# Sheet1.net
KiCad netlist of a schematic drawn in Altium Designer
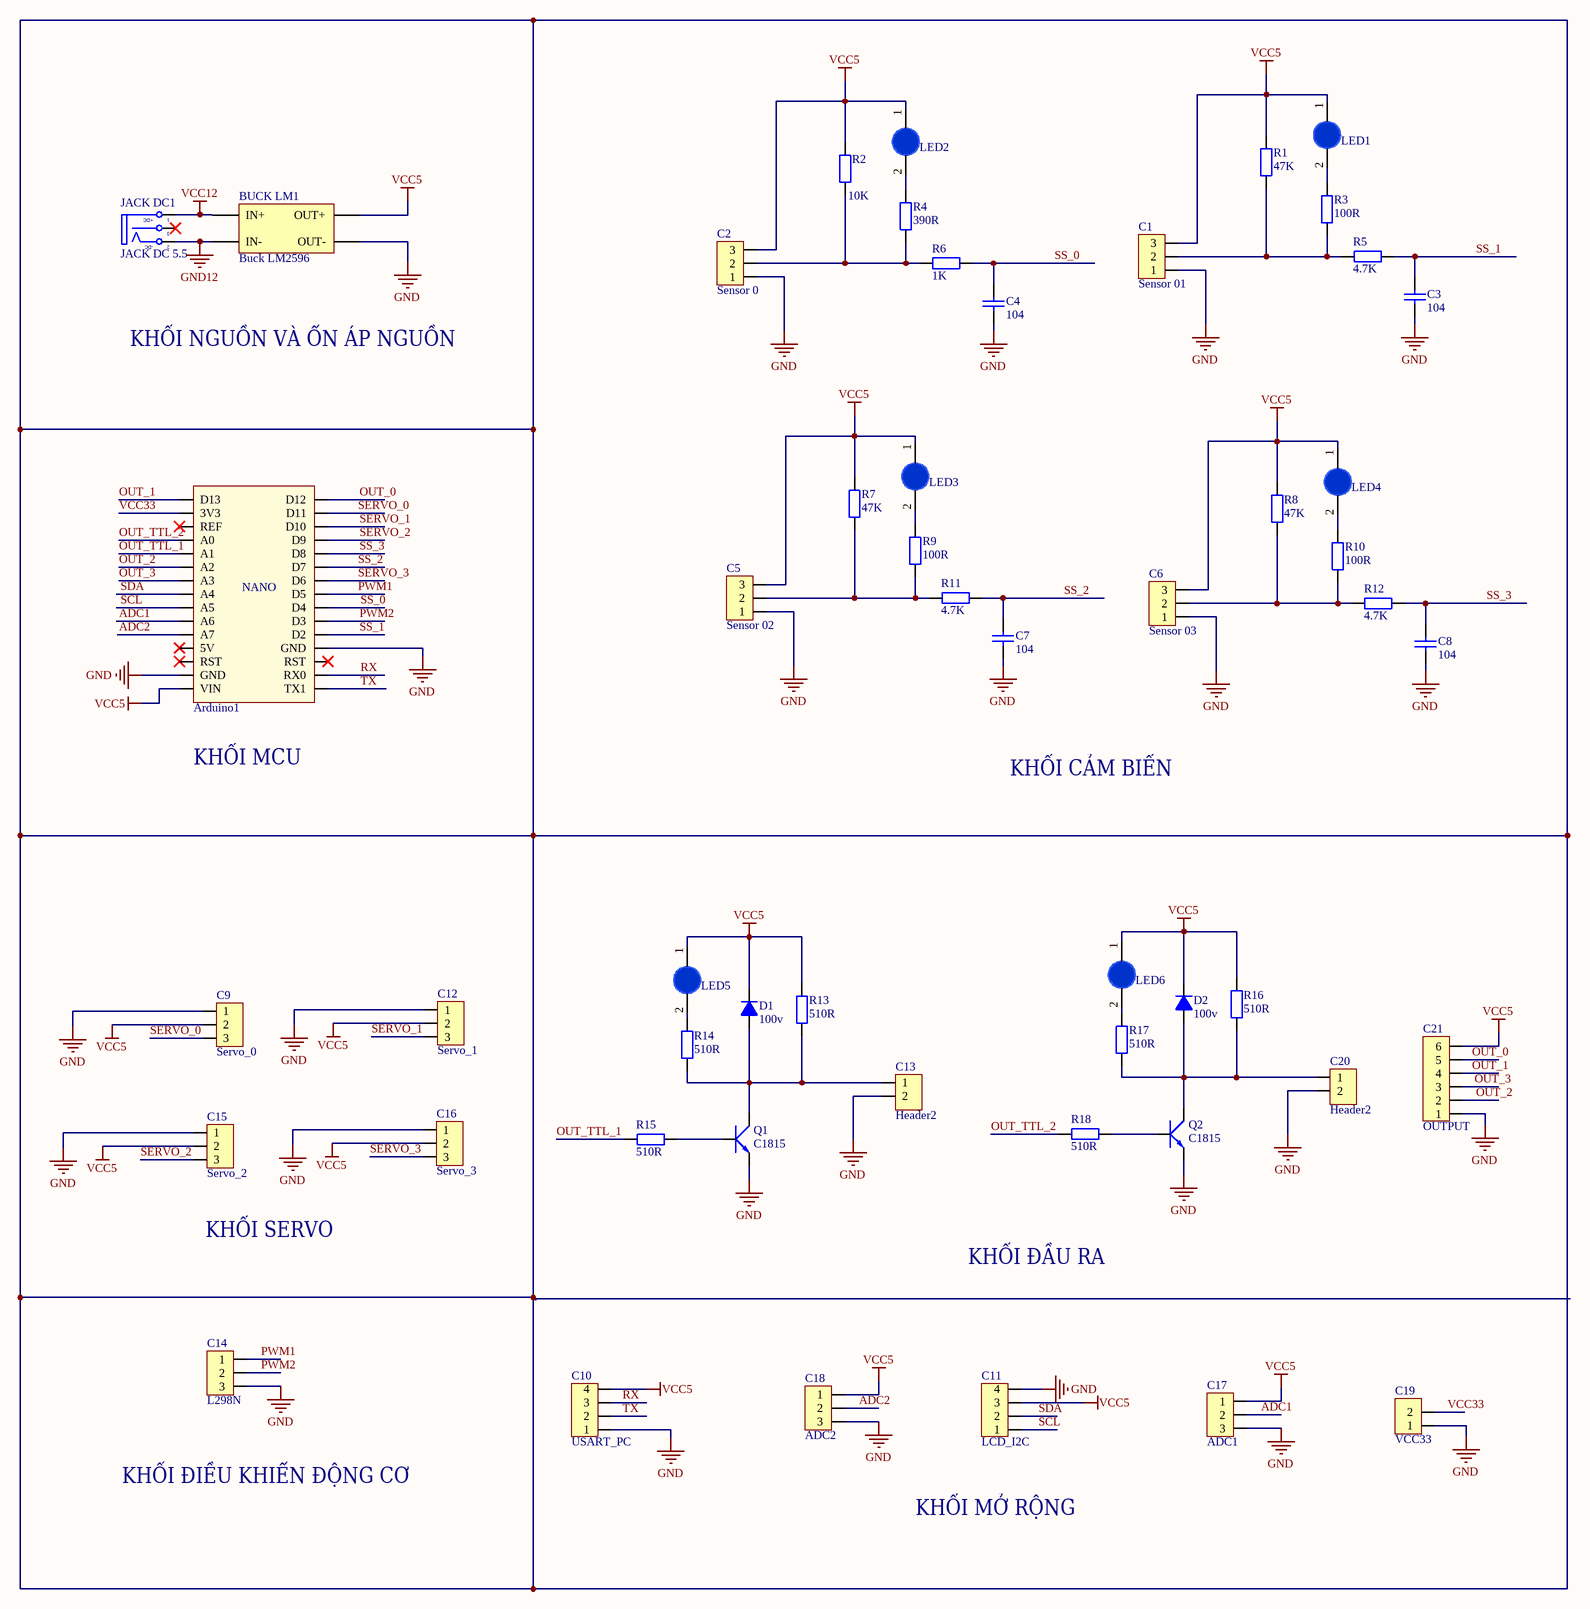
[diagram p0: Sheet1.SchDoc]

(export (version "E")
  (design (tool "Eeschema 10.0.6"))
  (components
    (comp (ref "Arduino1")
      (value "Arduino Nano")
      (footprint "Arduino Nano")
      (description "Arduino NANO")
      (libsource (lib "myLib_v1") (part "Arduino Nano"))
    )
    (comp (ref "BUCK LM1")
      (value "Buck LM2596")
      (footprint "BUCK LM2596")
      (libsource (lib "myLib_v1") (part "Buck LM2596"))
    )
    (comp (ref "C1")
      (value "Sensor 01")
      (footprint "Header3")
      (description "Header IDC, 3 x 1 Pin Vertical 2.54mm Pitch (Non-Boxed, Male)")
      (fields
        (field (name "MANUFACTURER") "Würth Elektronik eiSos GmbH")
        (field (name "PARTNO") "613002143121")
        (field (name "CREATED BY") "Karrer Zheng")
      )
      (libsource (lib "myLib_v1") (part "Header3"))
    )
    (comp (ref "C2")
      (value "Sensor 0")
      (footprint "Header3")
      (description "Header IDC, 3 x 1 Pin Vertical 2.54mm Pitch (Non-Boxed, Male)")
      (fields
        (field (name "MANUFACTURER") "Würth Elektronik eiSos GmbH")
        (field (name "PARTNO") "613002143121")
        (field (name "CREATED BY") "Karrer Zheng")
      )
      (libsource (lib "myLib_v1") (part "Header3"))
    )
    (comp (ref "C3")
      (value "104")
      (footprint "tu gom")
      (description "Cắm")
      (libsource (lib "Altium_Lib_by_KhueNguyenCreator") (part "Tu gom 104 50V"))
    )
    (comp (ref "C4")
      (value "104")
      (footprint "tu gom")
      (description "Cắm")
      (libsource (lib "Altium_Lib_by_KhueNguyenCreator") (part "Tu gom 104 50V"))
    )
    (comp (ref "C5")
      (value "Sensor 02")
      (footprint "Header3")
      (description "Header IDC, 3 x 1 Pin Vertical 2.54mm Pitch (Non-Boxed, Male)")
      (fields
        (field (name "MANUFACTURER") "Würth Elektronik eiSos GmbH")
        (field (name "PARTNO") "613002143121")
        (field (name "CREATED BY") "Karrer Zheng")
      )
      (libsource (lib "myLib_v1") (part "Header3"))
    )
    (comp (ref "C6")
      (value "Sensor 03")
      (footprint "Header3")
      (description "Header IDC, 3 x 1 Pin Vertical 2.54mm Pitch (Non-Boxed, Male)")
      (fields
        (field (name "MANUFACTURER") "Würth Elektronik eiSos GmbH")
        (field (name "PARTNO") "613002143121")
        (field (name "CREATED BY") "Karrer Zheng")
      )
      (libsource (lib "myLib_v1") (part "Header3"))
    )
    (comp (ref "C7")
      (value "104")
      (footprint "tu gom")
      (description "Cắm")
      (libsource (lib "Altium_Lib_by_KhueNguyenCreator") (part "Tu gom 104 50V"))
    )
    (comp (ref "C8")
      (value "104")
      (footprint "tu gom")
      (description "Cắm")
      (libsource (lib "Altium_Lib_by_KhueNguyenCreator") (part "Tu gom 104 50V"))
    )
    (comp (ref "C9")
      (value "Servo_0")
      (footprint "Header3")
      (description "Header IDC, 3 x 1 Pin Vertical 2.54mm Pitch (Non-Boxed, Male)")
      (fields
        (field (name "MANUFACTURER") "Würth Elektronik eiSos GmbH")
        (field (name "PARTNO") "613002143121")
        (field (name "CREATED BY") "Karrer Zheng")
      )
      (libsource (lib "") (part "Header3_1"))
    )
    (comp (ref "C10")
      (value "USART_PC")
      (footprint "Header4")
      (description "Header IDC, 4 x 1 Pin Vertical 2.54mm Pitch (Non-Boxed, Male)")
      (fields
        (field (name "MANUFACTURER") "Würth Elektronik eiSos GmbH")
        (field (name "PARTNO") "613002143121")
        (field (name "CREATED BY") "Karrer Zheng")
      )
      (libsource (lib "myLib_v1") (part "Header4"))
    )
    (comp (ref "C11")
      (value "LCD_I2C")
      (footprint "Header4")
      (description "Header IDC, 4 x 1 Pin Vertical 2.54mm Pitch (Non-Boxed, Male)")
      (fields
        (field (name "MANUFACTURER") "Würth Elektronik eiSos GmbH")
        (field (name "PARTNO") "613002143121")
        (field (name "CREATED BY") "Karrer Zheng")
      )
      (libsource (lib "myLib_v1") (part "Header4"))
    )
    (comp (ref "C12")
      (value "Servo_1")
      (footprint "Header3")
      (description "Header IDC, 3 x 1 Pin Vertical 2.54mm Pitch (Non-Boxed, Male)")
      (fields
        (field (name "MANUFACTURER") "Würth Elektronik eiSos GmbH")
        (field (name "PARTNO") "613002143121")
        (field (name "CREATED BY") "Karrer Zheng")
      )
      (libsource (lib "") (part "Header3_1"))
    )
    (comp (ref "C13")
      (value "Header2")
      (footprint "Header2")
      (description "Header IDC, 2 x 1 Pin Vertical 2.54mm Pitch (Non-Boxed, Male)")
      (fields
        (field (name "MANUFACTURER") "Würth Elektronik eiSos GmbH")
        (field (name "PARTNO") "613002143121")
        (field (name "CREATED BY") "Karrer Zheng")
      )
      (libsource (lib "myLib_v1") (part "Header2"))
    )
    (comp (ref "C14")
      (value "L298N")
      (footprint "Header3")
      (description "Header IDC, 3 x 1 Pin Vertical 2.54mm Pitch (Non-Boxed, Male)")
      (fields
        (field (name "MANUFACTURER") "Würth Elektronik eiSos GmbH")
        (field (name "PARTNO") "613002143121")
        (field (name "CREATED BY") "Karrer Zheng")
      )
      (libsource (lib "") (part "Header3_2"))
    )
    (comp (ref "C15")
      (value "Servo_2")
      (footprint "Header3")
      (description "Header IDC, 3 x 1 Pin Vertical 2.54mm Pitch (Non-Boxed, Male)")
      (fields
        (field (name "MANUFACTURER") "Würth Elektronik eiSos GmbH")
        (field (name "PARTNO") "613002143121")
        (field (name "CREATED BY") "Karrer Zheng")
      )
      (libsource (lib "") (part "Header3_1"))
    )
    (comp (ref "C16")
      (value "Servo_3")
      (footprint "Header3")
      (description "Header IDC, 3 x 1 Pin Vertical 2.54mm Pitch (Non-Boxed, Male)")
      (fields
        (field (name "MANUFACTURER") "Würth Elektronik eiSos GmbH")
        (field (name "PARTNO") "613002143121")
        (field (name "CREATED BY") "Karrer Zheng")
      )
      (libsource (lib "") (part "Header3_1"))
    )
    (comp (ref "C17")
      (value "ADC1")
      (footprint "Header3")
      (description "Header IDC, 3 x 1 Pin Vertical 2.54mm Pitch (Non-Boxed, Male)")
      (fields
        (field (name "MANUFACTURER") "Würth Elektronik eiSos GmbH")
        (field (name "PARTNO") "613002143121")
        (field (name "CREATED BY") "Karrer Zheng")
      )
      (libsource (lib "") (part "Header3_2"))
    )
    (comp (ref "C18")
      (value "ADC2")
      (footprint "Header3")
      (description "Header IDC, 3 x 1 Pin Vertical 2.54mm Pitch (Non-Boxed, Male)")
      (fields
        (field (name "MANUFACTURER") "Würth Elektronik eiSos GmbH")
        (field (name "PARTNO") "613002143121")
        (field (name "CREATED BY") "Karrer Zheng")
      )
      (libsource (lib "") (part "Header3_2"))
    )
    (comp (ref "C19")
      (value "VCC33")
      (footprint "Header2")
      (description "Header IDC, 2 x 1 Pin Vertical 2.54mm Pitch (Non-Boxed, Male)")
      (fields
        (field (name "MANUFACTURER") "Würth Elektronik eiSos GmbH")
        (field (name "PARTNO") "613002143121")
        (field (name "CREATED BY") "Karrer Zheng")
      )
      (libsource (lib "") (part "Header2_1"))
    )
    (comp (ref "C20")
      (value "Header2")
      (footprint "Header2")
      (description "Header IDC, 2 x 1 Pin Vertical 2.54mm Pitch (Non-Boxed, Male)")
      (fields
        (field (name "MANUFACTURER") "Würth Elektronik eiSos GmbH")
        (field (name "PARTNO") "613002143121")
        (field (name "CREATED BY") "Karrer Zheng")
      )
      (libsource (lib "myLib_v1") (part "Header2"))
    )
    (comp (ref "C21")
      (value "OUTPUT")
      (footprint "Header6")
      (description "Header IDC, 6 x 1 Pin Vertical 2.54mm Pitch (Non-Boxed, Male)")
      (fields
        (field (name "MANUFACTURER") "Würth Elektronik eiSos GmbH")
        (field (name "PARTNO") "613002143121")
        (field (name "CREATED BY") "Karrer Zheng")
      )
      (libsource (lib "myLib_v1") (part "Header6"))
    )
    (comp (ref "D1")
      (value "100v")
      (footprint "DIODE 0.5A")
      (description "Cắm")
      (libsource (lib "Altium_Lib_by_KhueNguyenCreator") (part "Diode 1N4148"))
    )
    (comp (ref "D2")
      (value "100v")
      (footprint "DIODE 0.5A")
      (description "Cắm")
      (libsource (lib "Altium_Lib_by_KhueNguyenCreator") (part "Diode 1N4148"))
    )
    (comp (ref "JACK DC1")
      (value "JACK DC 5.5")
      (footprint "JACK DC 5.5")
      (libsource (lib "Altium_Lib_by_KhueNguyenCreator") (part "JACK DC 5.5"))
    )
    (comp (ref "LED1")
      (value "LED 3mm")
      (footprint "LED-3MM-BLUE")
      (description "Cắm")
      (libsource (lib "myLib_v1") (part "LED 3mm Xanh Duong"))
    )
    (comp (ref "LED2")
      (value "LED 3mm")
      (footprint "LED-3MM-BLUE")
      (description "Cắm")
      (libsource (lib "myLib_v1") (part "LED 3mm Xanh Duong"))
    )
    (comp (ref "LED3")
      (value "LED 3mm")
      (footprint "LED-3MM-BLUE")
      (description "Cắm")
      (libsource (lib "myLib_v1") (part "LED 3mm Xanh Duong"))
    )
    (comp (ref "LED4")
      (value "LED 3mm")
      (footprint "LED-3MM-BLUE")
      (description "Cắm")
      (libsource (lib "myLib_v1") (part "LED 3mm Xanh Duong"))
    )
    (comp (ref "LED5")
      (value "LED 3mm")
      (footprint "LED-3MM-BLUE")
      (description "Cắm")
      (libsource (lib "myLib_v1") (part "LED 3mm Xanh Duong"))
    )
    (comp (ref "LED6")
      (value "LED 3mm")
      (footprint "LED-3MM-BLUE")
      (description "Cắm")
      (libsource (lib "myLib_v1") (part "LED 3mm Xanh Duong"))
    )
    (comp (ref "Q1")
      (value "C1815")
      (footprint "C1815_cam")
      (description "NPN 600mW, ECB")
      (libsource (lib "myLib_v1") (part "C1815"))
    )
    (comp (ref "Q2")
      (value "C1815")
      (footprint "C1815_cam")
      (description "NPN 600mW, ECB")
      (libsource (lib "myLib_v1") (part "C1815"))
    )
    (comp (ref "R1")
      (value "47K")
      (footprint "R1/4W")
      (description "Resistor 1/4W")
      (libsource (lib "myLib_v1") (part "R1/4W"))
    )
    (comp (ref "R2")
      (value "10K")
      (footprint "R1/4W")
      (description "Resistor 1/4W")
      (libsource (lib "myLib_v1") (part "R1/4W"))
    )
    (comp (ref "R3")
      (value "100R")
      (footprint "R1/4W")
      (description "Resistor 1/4W")
      (libsource (lib "myLib_v1") (part "R1/4W"))
    )
    (comp (ref "R4")
      (value "390R")
      (footprint "R1/4W")
      (description "Resistor 1/4W")
      (libsource (lib "myLib_v1") (part "R1/4W"))
    )
    (comp (ref "R5")
      (value "4.7K")
      (footprint "R1/4W")
      (description "Resistor 1/4W")
      (libsource (lib "myLib_v1") (part "R1/4W"))
    )
    (comp (ref "R6")
      (value "1K")
      (footprint "R1/4W")
      (description "Resistor 1/4W")
      (libsource (lib "myLib_v1") (part "R1/4W"))
    )
    (comp (ref "R7")
      (value "47K")
      (footprint "R1/4W")
      (description "Resistor 1/4W")
      (libsource (lib "myLib_v1") (part "R1/4W"))
    )
    (comp (ref "R8")
      (value "47K")
      (footprint "R1/4W")
      (description "Resistor 1/4W")
      (libsource (lib "myLib_v1") (part "R1/4W"))
    )
    (comp (ref "R9")
      (value "100R")
      (footprint "R1/4W")
      (description "Resistor 1/4W")
      (libsource (lib "myLib_v1") (part "R1/4W"))
    )
    (comp (ref "R10")
      (value "100R")
      (footprint "R1/4W")
      (description "Resistor 1/4W")
      (libsource (lib "myLib_v1") (part "R1/4W"))
    )
    (comp (ref "R11")
      (value "4.7K")
      (footprint "R1/4W")
      (description "Resistor 1/4W")
      (libsource (lib "myLib_v1") (part "R1/4W"))
    )
    (comp (ref "R12")
      (value "4.7K")
      (footprint "R1/4W")
      (description "Resistor 1/4W")
      (libsource (lib "myLib_v1") (part "R1/4W"))
    )
    (comp (ref "R13")
      (value "510R")
      (footprint "R1/4W")
      (description "Resistor 1/4W")
      (libsource (lib "myLib_v1") (part "R1/4W"))
    )
    (comp (ref "R14")
      (value "510R")
      (footprint "R1/4W")
      (description "Resistor 1/4W")
      (libsource (lib "myLib_v1") (part "R1/4W"))
    )
    (comp (ref "R15")
      (value "510R")
      (footprint "R1/4W")
      (description "Resistor 1/4W")
      (libsource (lib "myLib_v1") (part "R1/4W"))
    )
    (comp (ref "R16")
      (value "510R")
      (footprint "R1/4W")
      (description "Resistor 1/4W")
      (libsource (lib "myLib_v1") (part "R1/4W"))
    )
    (comp (ref "R17")
      (value "510R")
      (footprint "R1/4W")
      (description "Resistor 1/4W")
      (libsource (lib "myLib_v1") (part "R1/4W"))
    )
    (comp (ref "R18")
      (value "510R")
      (footprint "R1/4W")
      (description "Resistor 1/4W")
      (libsource (lib "myLib_v1") (part "R1/4W"))
    )
  )
  (nets
    (net (code "1") (name "/ADC1") (class "Default")
      (node (ref "Arduino1") (pin "A6") (pinfunction "A6_A6") (pintype "passive"))
      (node (ref "C17") (pin "2") (pinfunction "2_2") (pintype "passive"))
    )
    (net (code "2") (name "/ADC2") (class "Default")
      (node (ref "Arduino1") (pin "A7") (pinfunction "A7_A7") (pintype "passive"))
      (node (ref "C18") (pin "2") (pinfunction "2_2") (pintype "passive"))
    )
    (net (code "3") (name "/OUT_0") (class "Default")
      (node (ref "Arduino1") (pin "D12") (pinfunction "D12_D12") (pintype "passive"))
      (node (ref "C21") (pin "5") (pinfunction "5_5") (pintype "passive"))
    )
    (net (code "4") (name "/OUT_1") (class "Default")
      (node (ref "Arduino1") (pin "D13") (pinfunction "D13_D13") (pintype "passive"))
      (node (ref "C21") (pin "4") (pinfunction "4_4") (pintype "passive"))
    )
    (net (code "5") (name "/OUT_2") (class "Default")
      (node (ref "Arduino1") (pin "A2") (pinfunction "A2_A2") (pintype "passive"))
      (node (ref "C21") (pin "2") (pinfunction "2_2") (pintype "passive"))
    )
    (net (code "6") (name "/OUT_3") (class "Default")
      (node (ref "Arduino1") (pin "A3") (pinfunction "A3_A3") (pintype "passive"))
      (node (ref "C21") (pin "3") (pinfunction "3_3") (pintype "passive"))
    )
    (net (code "7") (name "/OUT_TTL_1") (class "Default")
      (node (ref "Arduino1") (pin "A1") (pinfunction "A1_A1") (pintype "passive"))
      (node (ref "R15") (pin "1") (pinfunction "1_1") (pintype "passive"))
    )
    (net (code "8") (name "/OUT_TTL_2") (class "Default")
      (node (ref "Arduino1") (pin "A0") (pinfunction "A0_A0") (pintype "passive"))
      (node (ref "R18") (pin "1") (pinfunction "1_1") (pintype "passive"))
    )
    (net (code "9") (name "/PWM1") (class "Default")
      (node (ref "Arduino1") (pin "D5") (pinfunction "D5_D5") (pintype "passive"))
      (node (ref "C14") (pin "1") (pinfunction "1_1") (pintype "passive"))
    )
    (net (code "10") (name "/PWM2") (class "Default")
      (node (ref "Arduino1") (pin "D3") (pinfunction "D3_D3") (pintype "passive"))
      (node (ref "C14") (pin "2") (pinfunction "2_2") (pintype "passive"))
    )
    (net (code "11") (name "/RX") (class "Default")
      (node (ref "Arduino1") (pin "RX0") (pinfunction "RX0_RX0") (pintype "passive"))
      (node (ref "C10") (pin "3") (pinfunction "3_3") (pintype "passive"))
    )
    (net (code "12") (name "/SCL") (class "Default")
      (node (ref "Arduino1") (pin "A5") (pinfunction "A5_A5") (pintype "passive"))
      (node (ref "C11") (pin "1") (pinfunction "1_1") (pintype "passive"))
    )
    (net (code "13") (name "/SDA") (class "Default")
      (node (ref "Arduino1") (pin "A4") (pinfunction "A4_A4") (pintype "passive"))
      (node (ref "C11") (pin "2") (pinfunction "2_2") (pintype "passive"))
    )
    (net (code "14") (name "/SERVO_0") (class "Default")
      (node (ref "Arduino1") (pin "D11") (pinfunction "D11_D11") (pintype "passive"))
      (node (ref "C9") (pin "3") (pinfunction "3_3") (pintype "passive"))
    )
    (net (code "15") (name "/SERVO_1") (class "Default")
      (node (ref "Arduino1") (pin "D10") (pinfunction "D10_D10") (pintype "passive"))
      (node (ref "C12") (pin "3") (pinfunction "3_3") (pintype "passive"))
    )
    (net (code "16") (name "/SERVO_2") (class "Default")
      (node (ref "Arduino1") (pin "D9") (pinfunction "D9_D9") (pintype "passive"))
      (node (ref "C15") (pin "3") (pinfunction "3_3") (pintype "passive"))
    )
    (net (code "17") (name "/SERVO_3") (class "Default")
      (node (ref "Arduino1") (pin "D6") (pinfunction "D6_D6") (pintype "passive"))
      (node (ref "C16") (pin "3") (pinfunction "3_3") (pintype "passive"))
    )
    (net (code "18") (name "/SS_0") (class "Default")
      (node (ref "Arduino1") (pin "D4") (pinfunction "D4_D4") (pintype "passive"))
      (node (ref "C4") (pin "1") (pinfunction "1_1") (pintype "passive"))
      (node (ref "R6") (pin "1") (pinfunction "1_1") (pintype "passive"))
    )
    (net (code "19") (name "/SS_1") (class "Default")
      (node (ref "Arduino1") (pin "D2") (pinfunction "D2_D2") (pintype "passive"))
      (node (ref "C3") (pin "1") (pinfunction "1_1") (pintype "passive"))
      (node (ref "R5") (pin "1") (pinfunction "1_1") (pintype "passive"))
    )
    (net (code "20") (name "/SS_2") (class "Default")
      (node (ref "Arduino1") (pin "D7") (pinfunction "D7_D7") (pintype "passive"))
      (node (ref "C7") (pin "1") (pinfunction "1_1") (pintype "passive"))
      (node (ref "R11") (pin "1") (pinfunction "1_1") (pintype "passive"))
    )
    (net (code "21") (name "/SS_3") (class "Default")
      (node (ref "Arduino1") (pin "D8") (pinfunction "D8_D8") (pintype "passive"))
      (node (ref "C8") (pin "1") (pinfunction "1_1") (pintype "passive"))
      (node (ref "R12") (pin "1") (pinfunction "1_1") (pintype "passive"))
    )
    (net (code "22") (name "/TX") (class "Default")
      (node (ref "Arduino1") (pin "TX1") (pinfunction "TX1_TX1") (pintype "passive"))
      (node (ref "C10") (pin "2") (pinfunction "2_2") (pintype "passive"))
    )
    (net (code "23") (name "/VCC33") (class "Default")
      (node (ref "Arduino1") (pin "3V3") (pinfunction "3V3_3V3") (pintype "passive"))
      (node (ref "C19") (pin "2") (pinfunction "2_2") (pintype "passive"))
    )
    (net (code "24") (name "GND") (class "Default")
      (node (ref "Arduino1") (pin "GND") (pinfunction "GND_GND") (pintype "passive"))
      (node (ref "BUCK LM1") (pin "3") (pinfunction "OUT-_3") (pintype "passive"))
      (node (ref "C1") (pin "1") (pinfunction "1_1") (pintype "passive"))
      (node (ref "C10") (pin "1") (pinfunction "1_1") (pintype "passive"))
      (node (ref "C11") (pin "4") (pinfunction "4_4") (pintype "passive"))
      (node (ref "C12") (pin "1") (pinfunction "1_1") (pintype "passive"))
      (node (ref "C13") (pin "2") (pinfunction "2_2") (pintype "passive"))
      (node (ref "C14") (pin "3") (pinfunction "3_3") (pintype "passive"))
      (node (ref "C15") (pin "1") (pinfunction "1_1") (pintype "passive"))
      (node (ref "C16") (pin "1") (pinfunction "1_1") (pintype "passive"))
      (node (ref "C17") (pin "3") (pinfunction "3_3") (pintype "passive"))
      (node (ref "C18") (pin "3") (pinfunction "3_3") (pintype "passive"))
      (node (ref "C19") (pin "1") (pinfunction "1_1") (pintype "passive"))
      (node (ref "C2") (pin "1") (pinfunction "1_1") (pintype "passive"))
      (node (ref "C20") (pin "2") (pinfunction "2_2") (pintype "passive"))
      (node (ref "C21") (pin "1") (pinfunction "1_1") (pintype "passive"))
      (node (ref "C3") (pin "2") (pinfunction "2_2") (pintype "passive"))
      (node (ref "C4") (pin "2") (pinfunction "2_2") (pintype "passive"))
      (node (ref "C5") (pin "1") (pinfunction "1_1") (pintype "passive"))
      (node (ref "C6") (pin "1") (pinfunction "1_1") (pintype "passive"))
      (node (ref "C7") (pin "2") (pinfunction "2_2") (pintype "passive"))
      (node (ref "C8") (pin "2") (pinfunction "2_2") (pintype "passive"))
      (node (ref "C9") (pin "1") (pinfunction "1_1") (pintype "passive"))
      (node (ref "Q1") (pin "1") (pinfunction "E_1") (pintype "passive"))
      (node (ref "Q2") (pin "1") (pinfunction "E_1") (pintype "passive"))
    )
    (net (code "25") (name "GND12") (class "Default")
      (node (ref "BUCK LM1") (pin "2") (pinfunction "IN-_2") (pintype "passive"))
      (node (ref "JACK DC1") (pin "2") (pinfunction "TN_2") (pintype "passive"))
    )
    (net (code "26") (name "Net-(C1-Pad2)") (class "Default")
      (node (ref "C1") (pin "2") (pinfunction "2_2") (pintype "passive"))
      (node (ref "R1") (pin "1") (pinfunction "1_1") (pintype "passive"))
      (node (ref "R3") (pin "1") (pinfunction "1_1") (pintype "passive"))
      (node (ref "R5") (pin "2") (pinfunction "2_2") (pintype "passive"))
    )
    (net (code "27") (name "Net-(C2-Pad2)") (class "Default")
      (node (ref "C2") (pin "2") (pinfunction "2_2") (pintype "passive"))
      (node (ref "R2") (pin "1") (pinfunction "1_1") (pintype "passive"))
      (node (ref "R4") (pin "1") (pinfunction "1_1") (pintype "passive"))
      (node (ref "R6") (pin "2") (pinfunction "2_2") (pintype "passive"))
    )
    (net (code "28") (name "Net-(C5-Pad2)") (class "Default")
      (node (ref "C5") (pin "2") (pinfunction "2_2") (pintype "passive"))
      (node (ref "R11") (pin "2") (pinfunction "2_2") (pintype "passive"))
      (node (ref "R7") (pin "1") (pinfunction "1_1") (pintype "passive"))
      (node (ref "R9") (pin "1") (pinfunction "1_1") (pintype "passive"))
    )
    (net (code "29") (name "Net-(C6-Pad2)") (class "Default")
      (node (ref "C6") (pin "2") (pinfunction "2_2") (pintype "passive"))
      (node (ref "R10") (pin "1") (pinfunction "1_1") (pintype "passive"))
      (node (ref "R12") (pin "2") (pinfunction "2_2") (pintype "passive"))
      (node (ref "R8") (pin "1") (pinfunction "1_1") (pintype "passive"))
    )
    (net (code "30") (name "Net-(D1-A)") (class "Default")
      (node (ref "C13") (pin "1") (pinfunction "1_1") (pintype "passive"))
      (node (ref "D1") (pin "1") (pinfunction "A_1") (pintype "passive"))
      (node (ref "Q1") (pin "2") (pinfunction "C_2") (pintype "passive"))
      (node (ref "R13") (pin "2") (pinfunction "2_2") (pintype "passive"))
      (node (ref "R14") (pin "2") (pinfunction "2_2") (pintype "passive"))
    )
    (net (code "31") (name "Net-(D2-A)") (class "Default")
      (node (ref "C20") (pin "1") (pinfunction "1_1") (pintype "passive"))
      (node (ref "D2") (pin "1") (pinfunction "A_1") (pintype "passive"))
      (node (ref "Q2") (pin "2") (pinfunction "C_2") (pintype "passive"))
      (node (ref "R16") (pin "2") (pinfunction "2_2") (pintype "passive"))
      (node (ref "R17") (pin "2") (pinfunction "2_2") (pintype "passive"))
    )
    (net (code "32") (name "Net-(LED1-K)") (class "Default")
      (node (ref "LED1") (pin "2") (pinfunction "K_2") (pintype "passive"))
      (node (ref "R3") (pin "2") (pinfunction "2_2") (pintype "passive"))
    )
    (net (code "33") (name "Net-(LED2-K)") (class "Default")
      (node (ref "LED2") (pin "2") (pinfunction "K_2") (pintype "passive"))
      (node (ref "R4") (pin "2") (pinfunction "2_2") (pintype "passive"))
    )
    (net (code "34") (name "Net-(LED3-K)") (class "Default")
      (node (ref "LED3") (pin "2") (pinfunction "K_2") (pintype "passive"))
      (node (ref "R9") (pin "2") (pinfunction "2_2") (pintype "passive"))
    )
    (net (code "35") (name "Net-(LED4-K)") (class "Default")
      (node (ref "LED4") (pin "2") (pinfunction "K_2") (pintype "passive"))
      (node (ref "R10") (pin "2") (pinfunction "2_2") (pintype "passive"))
    )
    (net (code "36") (name "Net-(LED5-K)") (class "Default")
      (node (ref "LED5") (pin "2") (pinfunction "K_2") (pintype "passive"))
      (node (ref "R14") (pin "1") (pinfunction "1_1") (pintype "passive"))
    )
    (net (code "37") (name "Net-(LED6-K)") (class "Default")
      (node (ref "LED6") (pin "2") (pinfunction "K_2") (pintype "passive"))
      (node (ref "R17") (pin "1") (pinfunction "1_1") (pintype "passive"))
    )
    (net (code "38") (name "Net-(Q1-B)") (class "Default")
      (node (ref "Q1") (pin "3") (pinfunction "B_3") (pintype "passive"))
      (node (ref "R15") (pin "2") (pinfunction "2_2") (pintype "passive"))
    )
    (net (code "39") (name "Net-(Q2-B)") (class "Default")
      (node (ref "Q2") (pin "3") (pinfunction "B_3") (pintype "passive"))
      (node (ref "R18") (pin "2") (pinfunction "2_2") (pintype "passive"))
    )
    (net (code "40") (name "VCC5") (class "Default")
      (node (ref "Arduino1") (pin "VIN") (pinfunction "VIN_VIN") (pintype "passive"))
      (node (ref "BUCK LM1") (pin "4") (pinfunction "OUT+_4") (pintype "passive"))
      (node (ref "C1") (pin "3") (pinfunction "3_3") (pintype "passive"))
      (node (ref "C10") (pin "4") (pinfunction "4_4") (pintype "passive"))
      (node (ref "C11") (pin "3") (pinfunction "3_3") (pintype "passive"))
      (node (ref "C12") (pin "2") (pinfunction "2_2") (pintype "passive"))
      (node (ref "C15") (pin "2") (pinfunction "2_2") (pintype "passive"))
      (node (ref "C16") (pin "2") (pinfunction "2_2") (pintype "passive"))
      (node (ref "C17") (pin "1") (pinfunction "1_1") (pintype "passive"))
      (node (ref "C18") (pin "1") (pinfunction "1_1") (pintype "passive"))
      (node (ref "C2") (pin "3") (pinfunction "3_3") (pintype "passive"))
      (node (ref "C21") (pin "6") (pinfunction "6_6") (pintype "passive"))
      (node (ref "C5") (pin "3") (pinfunction "3_3") (pintype "passive"))
      (node (ref "C6") (pin "3") (pinfunction "3_3") (pintype "passive"))
      (node (ref "C9") (pin "2") (pinfunction "2_2") (pintype "passive"))
      (node (ref "D1") (pin "2") (pinfunction "K_2") (pintype "passive"))
      (node (ref "D2") (pin "2") (pinfunction "K_2") (pintype "passive"))
      (node (ref "LED1") (pin "1") (pinfunction "A_1") (pintype "passive"))
      (node (ref "LED2") (pin "1") (pinfunction "A_1") (pintype "passive"))
      (node (ref "LED3") (pin "1") (pinfunction "A_1") (pintype "passive"))
      (node (ref "LED4") (pin "1") (pinfunction "A_1") (pintype "passive"))
      (node (ref "LED5") (pin "1") (pinfunction "A_1") (pintype "passive"))
      (node (ref "LED6") (pin "1") (pinfunction "A_1") (pintype "passive"))
      (node (ref "R1") (pin "2") (pinfunction "2_2") (pintype "passive"))
      (node (ref "R13") (pin "1") (pinfunction "1_1") (pintype "passive"))
      (node (ref "R16") (pin "1") (pinfunction "1_1") (pintype "passive"))
      (node (ref "R2") (pin "2") (pinfunction "2_2") (pintype "passive"))
      (node (ref "R7") (pin "2") (pinfunction "2_2") (pintype "passive"))
      (node (ref "R8") (pin "2") (pinfunction "2_2") (pintype "passive"))
    )
    (net (code "41") (name "VCC12") (class "Default")
      (node (ref "BUCK LM1") (pin "1") (pinfunction "IN+_1") (pintype "passive"))
      (node (ref "JACK DC1") (pin "1") (pinfunction "T_1") (pintype "passive"))
    )
    (net (code "42") (name "unconnected-(Arduino1-Pad5V)") (class "Default")
      (node (ref "Arduino1") (pin "5V") (pinfunction "5V_5V") (pintype "passive+no_connect"))
    )
    (net (code "43") (name "unconnected-(Arduino1-PadREF)") (class "Default")
      (node (ref "Arduino1") (pin "REF") (pinfunction "REF_REF") (pintype "passive+no_connect"))
    )
    (net (code "44") (name "unconnected-(Arduino1-PadRST)") (class "Default")
      (node (ref "Arduino1") (pin "RST") (pinfunction "RST_RST") (pintype "passive+no_connect"))
    )
    (net (code "45") (name "unconnected-(Arduino1-PadRST)_1") (class "Default")
      (node (ref "Arduino1") (pin "RST") (pinfunction "RST_RST") (pintype "passive+no_connect"))
    )
    (net (code "46") (name "unconnected-(JACK DC1-S-Pad3)") (class "Default")
      (node (ref "JACK DC1") (pin "3") (pinfunction "S_3") (pintype "power_in+no_connect"))
    )
  )
)
